# 06-AUDIO.net
KiCad netlist of a schematic drawn in Altium Designer
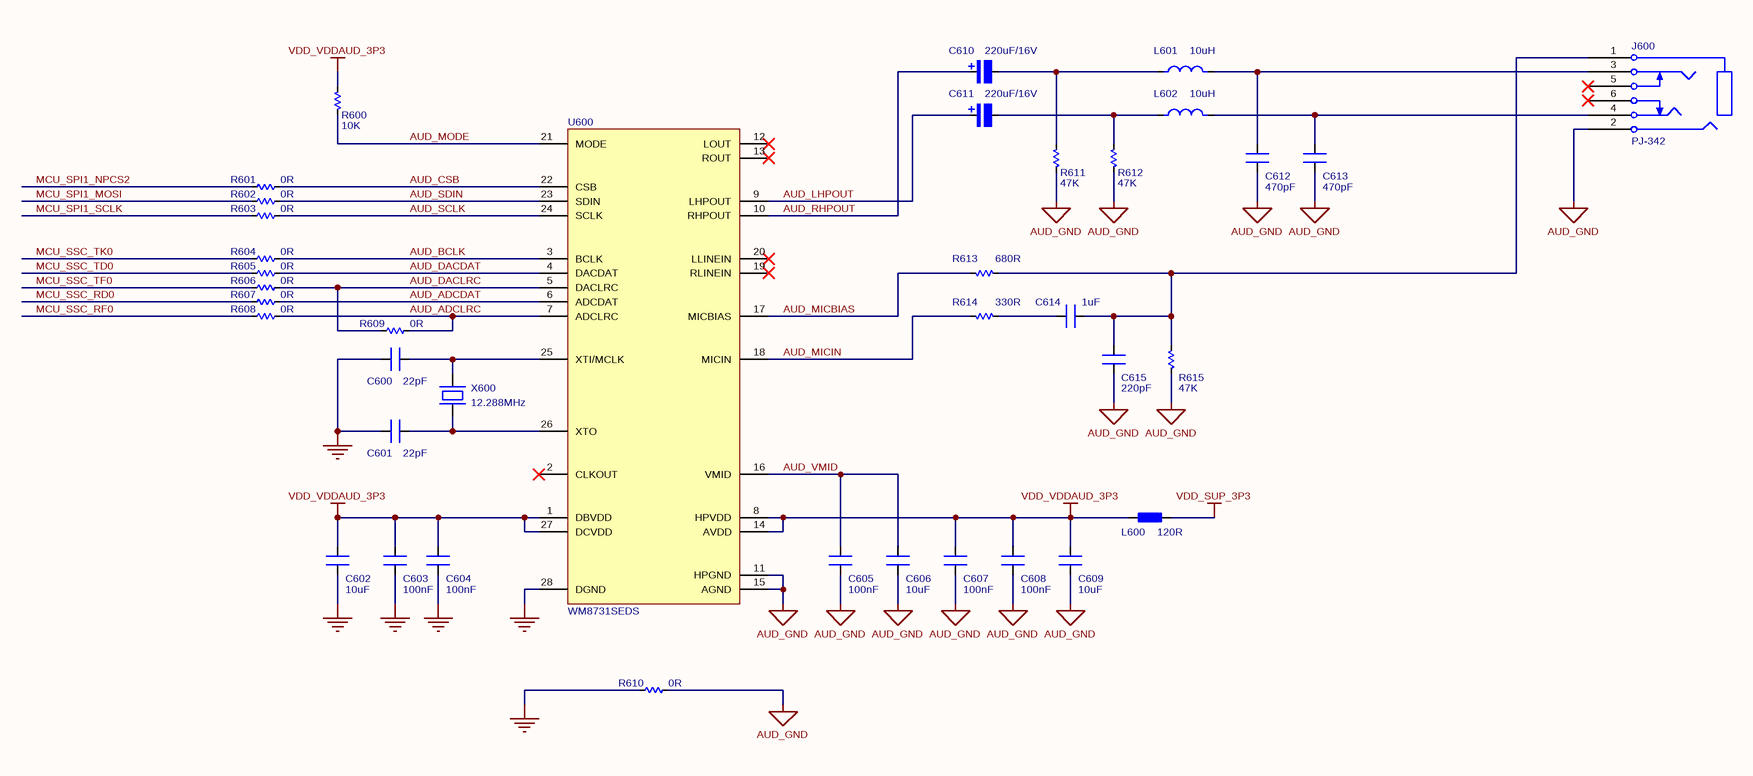
[diagram p0: 06-AUDIO.SchDoc]

(export (version "E")
  (design (tool "Eeschema 10.0.6"))
  (components
    (comp (ref "C600")
      (value "22pF")
      (footprint "CN-SMD-0603")
      (description "Ceramic Capacitor SMD 0603 22pF ±20% 10V")
      (fields (field (name "Comment") "Capacitor"))
      (libsource (lib "AS50") (part "Cap"))
    )
    (comp (ref "C601")
      (value "22pF")
      (footprint "CN-SMD-0603")
      (description "Ceramic Capacitor SMD 0603 22pF ±20% 10V")
      (fields (field (name "Comment") "Capacitor"))
      (libsource (lib "AS50") (part "Cap"))
    )
    (comp (ref "C602")
      (value "10uF")
      (footprint "CN-SMD-0603")
      (description "Ceramic Capacitor SMD 0603 10uF ±20% 10V")
      (fields (field (name "Comment") "Capacitor"))
      (libsource (lib "AS50") (part "Cap"))
    )
    (comp (ref "C603")
      (value "100nF")
      (footprint "CN-SMD-0603")
      (description "Ceramic Capacitor SMD 0603 100nF ±20% 10V")
      (fields (field (name "Comment") "Capacitor"))
      (libsource (lib "AS50") (part "Cap"))
    )
    (comp (ref "C604")
      (value "100nF")
      (footprint "CN-SMD-0603")
      (description "Ceramic Capacitor SMD 0603 100nF ±20% 10V")
      (fields (field (name "Comment") "Capacitor"))
      (libsource (lib "AS50") (part "Cap"))
    )
    (comp (ref "C605")
      (value "100nF")
      (footprint "CN-SMD-0603")
      (description "Ceramic Capacitor SMD 0603 100nF ±20% 10V")
      (fields (field (name "Comment") "Capacitor"))
      (libsource (lib "AS50") (part "Cap"))
    )
    (comp (ref "C606")
      (value "10uF")
      (footprint "CN-SMD-0603")
      (description "Ceramic Capacitor SMD 0603 10uF ±20% 10V")
      (fields (field (name "Comment") "Capacitor"))
      (libsource (lib "AS50") (part "Cap"))
    )
    (comp (ref "C607")
      (value "100nF")
      (footprint "CN-SMD-0603")
      (description "Ceramic Capacitor SMD 0603 100nF ±20% 10V")
      (fields (field (name "Comment") "Capacitor"))
      (libsource (lib "AS50") (part "Cap"))
    )
    (comp (ref "C608")
      (value "100nF")
      (footprint "CN-SMD-0603")
      (description "Ceramic Capacitor SMD 0603 100nF ±20% 10V")
      (fields (field (name "Comment") "Capacitor"))
      (libsource (lib "AS50") (part "Cap"))
    )
    (comp (ref "C609")
      (value "10uF")
      (footprint "CN-SMD-0603")
      (description "Ceramic Capacitor SMD 0603 10uF ±20% 10V")
      (fields (field (name "Comment") "Capacitor"))
      (libsource (lib "AS50") (part "Cap"))
    )
    (comp (ref "C610")
      (value "220uF/16V")
      (footprint "C-TAL-SMD-3216-18")
      (description "Tantalum Capacitor SMD 3216 220uF ±20% 16V")
      (fields (field (name "Comment") "Cap_Tantalum"))
      (libsource (lib "AS50") (part "Cap_Tantalum"))
    )
    (comp (ref "C611")
      (value "220uF/16V")
      (footprint "C-TAL-SMD-3216-18")
      (description "Tantalum Capacitor SMD 3216 220uF ±20% 16V")
      (fields (field (name "Comment") "Cap_Tantalum"))
      (libsource (lib "AS50") (part "Cap_Tantalum"))
    )
    (comp (ref "C612")
      (value "470pF")
      (footprint "CN-SMD-0603")
      (description "Ceramic Capacitor SMD 0603 470pF ±20% 10V")
      (fields (field (name "Comment") "Capacitor"))
      (libsource (lib "AS50") (part "Cap"))
    )
    (comp (ref "C613")
      (value "470pF")
      (footprint "CN-SMD-0603")
      (description "Ceramic Capacitor SMD 0603 470pF ±20% 10V")
      (fields (field (name "Comment") "Capacitor"))
      (libsource (lib "AS50") (part "Cap"))
    )
    (comp (ref "C614")
      (value "1uF")
      (footprint "CN-SMD-0603")
      (description "Ceramic Capacitor SMD 0603 1uF ±20% 10V")
      (fields (field (name "Comment") "Capacitor"))
      (libsource (lib "AS50") (part "Cap"))
    )
    (comp (ref "C615")
      (value "220pF")
      (footprint "CN-SMD-0603")
      (description "Ceramic Capacitor SMD 0603 220pF ±20% 10V")
      (fields (field (name "Comment") "Capacitor"))
      (libsource (lib "AS50") (part "Cap"))
    )
    (comp (ref "J600")
      (value "PJ-342")
      (footprint "AUDIO_PJ-342")
      (description "Audio connector PJ-342 3.5mm 4-pole")
      (libsource (lib "AS50") (part "PJ-342"))
    )
    (comp (ref "L600")
      (value "120R")
      (footprint "L-SMD-0603")
      (description "Ferrite bead SMD 0603 120 Ohm @100MHz")
      (fields (field (name "Comment") "Ferrite bead"))
      (libsource (lib "AS50") (part "Ferrite bead"))
    )
    (comp (ref "L601")
      (value "10uH")
      (footprint "L-SMD-0603")
      (description "Common Inductor SMD 0603 10uH ±20%")
      (fields (field (name "Comment") "Inductor"))
      (libsource (lib "AS50") (part "Inductor"))
    )
    (comp (ref "L602")
      (value "10uH")
      (footprint "L-SMD-0603")
      (description "Common Inductor SMD 0603 10uH ±20%")
      (fields (field (name "Comment") "Inductor"))
      (libsource (lib "AS50") (part "Inductor"))
    )
    (comp (ref "R600")
      (value "10K")
      (footprint "RES-SMD-0603")
      (description "Resistor SMD 0603 10K 1% 0.1W")
      (fields (field (name "Comment") "Resistor"))
      (libsource (lib "AS50") (part "Res"))
    )
    (comp (ref "R601")
      (value "0R")
      (footprint "RES-SMD-0603")
      (description "Resistor SMD 0603 0R 1% 0.1W")
      (fields (field (name "Comment") "Resistor"))
      (libsource (lib "AS50") (part "Res"))
    )
    (comp (ref "R602")
      (value "0R")
      (footprint "RES-SMD-0603")
      (description "Resistor SMD 0603 0R 1% 0.1W")
      (fields (field (name "Comment") "Resistor"))
      (libsource (lib "AS50") (part "Res"))
    )
    (comp (ref "R603")
      (value "0R")
      (footprint "RES-SMD-0603")
      (description "Resistor SMD 0603 0R 1% 0.1W")
      (fields (field (name "Comment") "Resistor"))
      (libsource (lib "AS50") (part "Res"))
    )
    (comp (ref "R604")
      (value "0R")
      (footprint "RES-SMD-0603")
      (description "Resistor SMD 0603 0R 1% 0.1W")
      (fields (field (name "Comment") "Resistor"))
      (libsource (lib "AS50") (part "Res"))
    )
    (comp (ref "R605")
      (value "0R")
      (footprint "RES-SMD-0603")
      (description "Resistor SMD 0603 0R 1% 0.1W")
      (fields (field (name "Comment") "Resistor"))
      (libsource (lib "AS50") (part "Res"))
    )
    (comp (ref "R606")
      (value "0R")
      (footprint "RES-SMD-0603")
      (description "Resistor SMD 0603 0R 1% 0.1W")
      (fields (field (name "Comment") "Resistor"))
      (libsource (lib "AS50") (part "Res"))
    )
    (comp (ref "R607")
      (value "0R")
      (footprint "RES-SMD-0603")
      (description "Resistor SMD 0603 0R 1% 0.1W")
      (fields (field (name "Comment") "Resistor"))
      (libsource (lib "AS50") (part "Res"))
    )
    (comp (ref "R608")
      (value "0R")
      (footprint "RES-SMD-0603")
      (description "Resistor SMD 0603 0R 1% 0.1W")
      (fields (field (name "Comment") "Resistor"))
      (libsource (lib "AS50") (part "Res"))
    )
    (comp (ref "R609")
      (value "0R")
      (footprint "RES-SMD-0603")
      (description "Resistor SMD 0603 0R 1% 0.1W")
      (fields (field (name "Comment") "Resistor"))
      (libsource (lib "AS50") (part "Res"))
    )
    (comp (ref "R610")
      (value "0R")
      (footprint "RES-SMD-0603")
      (description "Resistor SMD 0603 0R 1% 0.1W")
      (fields (field (name "Comment") "Resistor"))
      (libsource (lib "AS50") (part "Res"))
    )
    (comp (ref "R611")
      (value "47K")
      (footprint "RES-SMD-0603")
      (description "Resistor SMD 0603 47K 1% 0.1W")
      (fields (field (name "Comment") "Resistor"))
      (libsource (lib "AS50") (part "Res"))
    )
    (comp (ref "R612")
      (value "47K")
      (footprint "RES-SMD-0603")
      (description "Resistor SMD 0603 47K 1% 0.1W")
      (fields (field (name "Comment") "Resistor"))
      (libsource (lib "AS50") (part "Res"))
    )
    (comp (ref "R613")
      (value "680R")
      (footprint "RES-SMD-0603")
      (description "Resistor SMD 0603 680R 1% 0.1W")
      (fields (field (name "Comment") "Resistor"))
      (libsource (lib "AS50") (part "Res"))
    )
    (comp (ref "R614")
      (value "330R")
      (footprint "RES-SMD-0603")
      (description "Resistor SMD 0603 330R 1% 0.1W")
      (fields (field (name "Comment") "Resistor"))
      (libsource (lib "AS50") (part "Res"))
    )
    (comp (ref "R615")
      (value "47K")
      (footprint "RES-SMD-0603")
      (description "Resistor SMD 0603 47K 1% 0.1W")
      (fields (field (name "Comment") "Resistor"))
      (libsource (lib "AS50") (part "Res"))
    )
    (comp (ref "U600")
      (value "WM8731SEDS")
      (footprint "SSOP65P780X200-28N")
      (description "Cirrus Logic Portable Internet Audio CODEC with Headphone Driver and Programmable Sample Rates")
      (libsource (lib "AS50") (part "WM8731SEDS"))
    )
    (comp (ref "X600")
      (value "12.288MHz")
      (footprint "XT-SMD-5032-2P")
      (description "Crystal Oscillator 12.288MHz SMD-5032 2-pin")
      (fields (field (name "Comment") "Crystal"))
      (libsource (lib "AS50") (part "XT2"))
    )
  )
  (nets
    (net (code "1") (name "/AUD_ADCDAT") (class "Default")
      (node (ref "R607") (pin "1") (pinfunction "1_1") (pintype "passive"))
      (node (ref "U600") (pin "6") (pinfunction "ADCDAT_6") (pintype "passive"))
    )
    (net (code "2") (name "/AUD_ADCLRC") (class "Default")
      (node (ref "R608") (pin "1") (pinfunction "1_1") (pintype "passive"))
      (node (ref "R609") (pin "1") (pinfunction "1_1") (pintype "passive"))
      (node (ref "U600") (pin "7") (pinfunction "ADCLRC_7") (pintype "passive"))
    )
    (net (code "3") (name "/AUD_BCLK") (class "Default")
      (node (ref "R604") (pin "1") (pinfunction "1_1") (pintype "passive"))
      (node (ref "U600") (pin "3") (pinfunction "BCLK_3") (pintype "passive"))
    )
    (net (code "4") (name "/AUD_CSB") (class "Default")
      (node (ref "R601") (pin "1") (pinfunction "1_1") (pintype "passive"))
      (node (ref "U600") (pin "22") (pinfunction "CSB_22") (pintype "passive"))
    )
    (net (code "5") (name "/AUD_DACDAT") (class "Default")
      (node (ref "R605") (pin "1") (pinfunction "1_1") (pintype "passive"))
      (node (ref "U600") (pin "4") (pinfunction "DACDAT_4") (pintype "passive"))
    )
    (net (code "6") (name "/AUD_DACLRC") (class "Default")
      (node (ref "R606") (pin "1") (pinfunction "1_1") (pintype "passive"))
      (node (ref "R609") (pin "2") (pinfunction "2_2") (pintype "passive"))
      (node (ref "U600") (pin "5") (pinfunction "DACLRC_5") (pintype "passive"))
    )
    (net (code "7") (name "/AUD_LHPOUT") (class "Default")
      (node (ref "C611") (pin "1") (pinfunction "1_1") (pintype "passive"))
      (node (ref "U600") (pin "9") (pinfunction "LHPOUT_9") (pintype "passive"))
    )
    (net (code "8") (name "/AUD_MICBIAS") (class "Default")
      (node (ref "R613") (pin "1") (pinfunction "1_1") (pintype "passive"))
      (node (ref "U600") (pin "17") (pinfunction "MICBIAS_17") (pintype "passive"))
    )
    (net (code "9") (name "/AUD_MICIN") (class "Default")
      (node (ref "R614") (pin "1") (pinfunction "1_1") (pintype "passive"))
      (node (ref "U600") (pin "18") (pinfunction "MICIN_18") (pintype "passive"))
    )
    (net (code "10") (name "/AUD_MODE") (class "Default")
      (node (ref "R600") (pin "2") (pinfunction "2_2") (pintype "passive"))
      (node (ref "U600") (pin "21") (pinfunction "MODE_21") (pintype "passive"))
    )
    (net (code "11") (name "/AUD_RHPOUT") (class "Default")
      (node (ref "C610") (pin "1") (pinfunction "1_1") (pintype "passive"))
      (node (ref "U600") (pin "10") (pinfunction "RHPOUT_10") (pintype "passive"))
    )
    (net (code "12") (name "/AUD_SCLK") (class "Default")
      (node (ref "R603") (pin "1") (pinfunction "1_1") (pintype "passive"))
      (node (ref "U600") (pin "24") (pinfunction "SCLK_24") (pintype "passive"))
    )
    (net (code "13") (name "/AUD_SDIN") (class "Default")
      (node (ref "R602") (pin "1") (pinfunction "1_1") (pintype "passive"))
      (node (ref "U600") (pin "23") (pinfunction "SDIN_23") (pintype "passive"))
    )
    (net (code "14") (name "/AUD_VMID") (class "Default")
      (node (ref "C605") (pin "2") (pinfunction "2_2") (pintype "passive"))
      (node (ref "C606") (pin "2") (pinfunction "2_2") (pintype "passive"))
      (node (ref "U600") (pin "16") (pinfunction "VMID_16") (pintype "passive"))
    )
    (net (code "15") (name "/MCU_SPI1_MOSI") (class "Default")
      (node (ref "R602") (pin "2") (pinfunction "2_2") (pintype "passive"))
    )
    (net (code "16") (name "/MCU_SPI1_NPCS2") (class "Default")
      (node (ref "R601") (pin "2") (pinfunction "2_2") (pintype "passive"))
    )
    (net (code "17") (name "/MCU_SPI1_SCLK") (class "Default")
      (node (ref "R603") (pin "2") (pinfunction "2_2") (pintype "passive"))
    )
    (net (code "18") (name "/MCU_SSC_RD0") (class "Default")
      (node (ref "R607") (pin "2") (pinfunction "2_2") (pintype "passive"))
    )
    (net (code "19") (name "/MCU_SSC_RF0") (class "Default")
      (node (ref "R608") (pin "2") (pinfunction "2_2") (pintype "passive"))
    )
    (net (code "20") (name "/MCU_SSC_TD0") (class "Default")
      (node (ref "R605") (pin "2") (pinfunction "2_2") (pintype "passive"))
    )
    (net (code "21") (name "/MCU_SSC_TF0") (class "Default")
      (node (ref "R606") (pin "2") (pinfunction "2_2") (pintype "passive"))
    )
    (net (code "22") (name "/MCU_SSC_TK0") (class "Default")
      (node (ref "R604") (pin "2") (pinfunction "2_2") (pintype "passive"))
    )
    (net (code "23") (name "AUD_GND") (class "Default")
      (node (ref "C605") (pin "1") (pinfunction "1_1") (pintype "passive"))
      (node (ref "C606") (pin "1") (pinfunction "1_1") (pintype "passive"))
      (node (ref "C607") (pin "1") (pinfunction "1_1") (pintype "passive"))
      (node (ref "C608") (pin "1") (pinfunction "1_1") (pintype "passive"))
      (node (ref "C609") (pin "1") (pinfunction "1_1") (pintype "passive"))
      (node (ref "C612") (pin "1") (pinfunction "1_1") (pintype "passive"))
      (node (ref "C613") (pin "1") (pinfunction "1_1") (pintype "passive"))
      (node (ref "C615") (pin "1") (pinfunction "1_1") (pintype "passive"))
      (node (ref "J600") (pin "2") (pinfunction "GND_2") (pintype "passive"))
      (node (ref "R610") (pin "1") (pinfunction "1_1") (pintype "passive"))
      (node (ref "R611") (pin "2") (pinfunction "2_2") (pintype "passive"))
      (node (ref "R612") (pin "2") (pinfunction "2_2") (pintype "passive"))
      (node (ref "R615") (pin "2") (pinfunction "2_2") (pintype "passive"))
      (node (ref "U600") (pin "11") (pinfunction "HPGND_11") (pintype "passive"))
      (node (ref "U600") (pin "15") (pinfunction "AGND_15") (pintype "passive"))
    )
    (net (code "24") (name "GND") (class "Default")
      (node (ref "C600") (pin "2") (pinfunction "2_2") (pintype "passive"))
      (node (ref "C601") (pin "2") (pinfunction "2_2") (pintype "passive"))
      (node (ref "C602") (pin "1") (pinfunction "1_1") (pintype "passive"))
      (node (ref "C603") (pin "1") (pinfunction "1_1") (pintype "passive"))
      (node (ref "C604") (pin "1") (pinfunction "1_1") (pintype "passive"))
      (node (ref "R610") (pin "2") (pinfunction "2_2") (pintype "passive"))
      (node (ref "U600") (pin "28") (pinfunction "DGND_28") (pintype "passive"))
    )
    (net (code "25") (name "Net-(C610-Pad2)") (class "Default")
      (node (ref "C610") (pin "2") (pinfunction "2_2") (pintype "passive"))
      (node (ref "L601") (pin "2") (pinfunction "2_2") (pintype "passive"))
      (node (ref "R611") (pin "1") (pinfunction "1_1") (pintype "passive"))
    )
    (net (code "26") (name "Net-(C611-Pad2)") (class "Default")
      (node (ref "C611") (pin "2") (pinfunction "2_2") (pintype "passive"))
      (node (ref "L602") (pin "2") (pinfunction "2_2") (pintype "passive"))
      (node (ref "R612") (pin "1") (pinfunction "1_1") (pintype "passive"))
    )
    (net (code "27") (name "Net-(C614-Pad2)") (class "Default")
      (node (ref "C614") (pin "2") (pinfunction "2_2") (pintype "passive"))
      (node (ref "R614") (pin "2") (pinfunction "2_2") (pintype "passive"))
    )
    (net (code "28") (name "Net-(J600-LEFT)") (class "Default")
      (node (ref "C613") (pin "2") (pinfunction "2_2") (pintype "passive"))
      (node (ref "J600") (pin "4") (pinfunction "LEFT_4") (pintype "passive"))
      (node (ref "L602") (pin "1") (pinfunction "1_1") (pintype "passive"))
    )
    (net (code "29") (name "Net-(J600-MIC)") (class "Default")
      (node (ref "C614") (pin "1") (pinfunction "1_1") (pintype "passive"))
      (node (ref "C615") (pin "2") (pinfunction "2_2") (pintype "passive"))
      (node (ref "J600") (pin "1") (pinfunction "MIC_1") (pintype "passive"))
      (node (ref "R613") (pin "2") (pinfunction "2_2") (pintype "passive"))
      (node (ref "R615") (pin "1") (pinfunction "1_1") (pintype "passive"))
    )
    (net (code "30") (name "Net-(J600-RIGHT)") (class "Default")
      (node (ref "C612") (pin "2") (pinfunction "2_2") (pintype "passive"))
      (node (ref "J600") (pin "3") (pinfunction "RIGHT_3") (pintype "passive"))
      (node (ref "L601") (pin "1") (pinfunction "1_1") (pintype "passive"))
    )
    (net (code "31") (name "Net-(U600-XTI{slash}MCLK)") (class "Default")
      (node (ref "C600") (pin "1") (pinfunction "1_1") (pintype "passive"))
      (node (ref "U600") (pin "25") (pinfunction "XTI/MCLK_25") (pintype "passive"))
      (node (ref "X600") (pin "1") (pinfunction "1_1") (pintype "passive"))
    )
    (net (code "32") (name "Net-(U600-XTO)") (class "Default")
      (node (ref "C601") (pin "1") (pinfunction "1_1") (pintype "passive"))
      (node (ref "U600") (pin "26") (pinfunction "XTO_26") (pintype "passive"))
      (node (ref "X600") (pin "2") (pinfunction "2_2") (pintype "passive"))
    )
    (net (code "33") (name "VDD_SUP_3P3") (class "Default")
      (node (ref "L600") (pin "2") (pinfunction "2_2") (pintype "passive"))
    )
    (net (code "34") (name "VDD_VDDAUD_3P3") (class "Default")
      (node (ref "C602") (pin "2") (pinfunction "2_2") (pintype "passive"))
      (node (ref "C603") (pin "2") (pinfunction "2_2") (pintype "passive"))
      (node (ref "C604") (pin "2") (pinfunction "2_2") (pintype "passive"))
      (node (ref "C607") (pin "2") (pinfunction "2_2") (pintype "passive"))
      (node (ref "C608") (pin "2") (pinfunction "2_2") (pintype "passive"))
      (node (ref "C609") (pin "2") (pinfunction "2_2") (pintype "passive"))
      (node (ref "L600") (pin "1") (pinfunction "1_1") (pintype "passive"))
      (node (ref "R600") (pin "1") (pinfunction "1_1") (pintype "passive"))
      (node (ref "U600") (pin "1") (pinfunction "DBVDD_1") (pintype "passive"))
      (node (ref "U600") (pin "14") (pinfunction "AVDD_14") (pintype "passive"))
      (node (ref "U600") (pin "27") (pinfunction "DCVDD_27") (pintype "passive"))
      (node (ref "U600") (pin "8") (pinfunction "HPVDD_8") (pintype "passive"))
    )
    (net (code "35") (name "unconnected-(J600-Pad5)") (class "Default")
      (node (ref "J600") (pin "5") (pintype "passive+no_connect"))
    )
    (net (code "36") (name "unconnected-(J600-Pad6)") (class "Default")
      (node (ref "J600") (pin "6") (pintype "passive+no_connect"))
    )
    (net (code "37") (name "unconnected-(U600-CLKOUT-Pad2)") (class "Default")
      (node (ref "U600") (pin "2") (pinfunction "CLKOUT_2") (pintype "passive+no_connect"))
    )
    (net (code "38") (name "unconnected-(U600-LLINEIN-Pad20)") (class "Default")
      (node (ref "U600") (pin "20") (pinfunction "LLINEIN_20") (pintype "passive+no_connect"))
    )
    (net (code "39") (name "unconnected-(U600-LOUT-Pad12)") (class "Default")
      (node (ref "U600") (pin "12") (pinfunction "LOUT_12") (pintype "passive+no_connect"))
    )
    (net (code "40") (name "unconnected-(U600-RLINEIN-Pad19)") (class "Default")
      (node (ref "U600") (pin "19") (pinfunction "RLINEIN_19") (pintype "passive+no_connect"))
    )
    (net (code "41") (name "unconnected-(U600-ROUT-Pad13)") (class "Default")
      (node (ref "U600") (pin "13") (pinfunction "ROUT_13") (pintype "passive+no_connect"))
    )
  )
)
